# car.net
KiCad netlist of a schematic drawn in Altium Designer
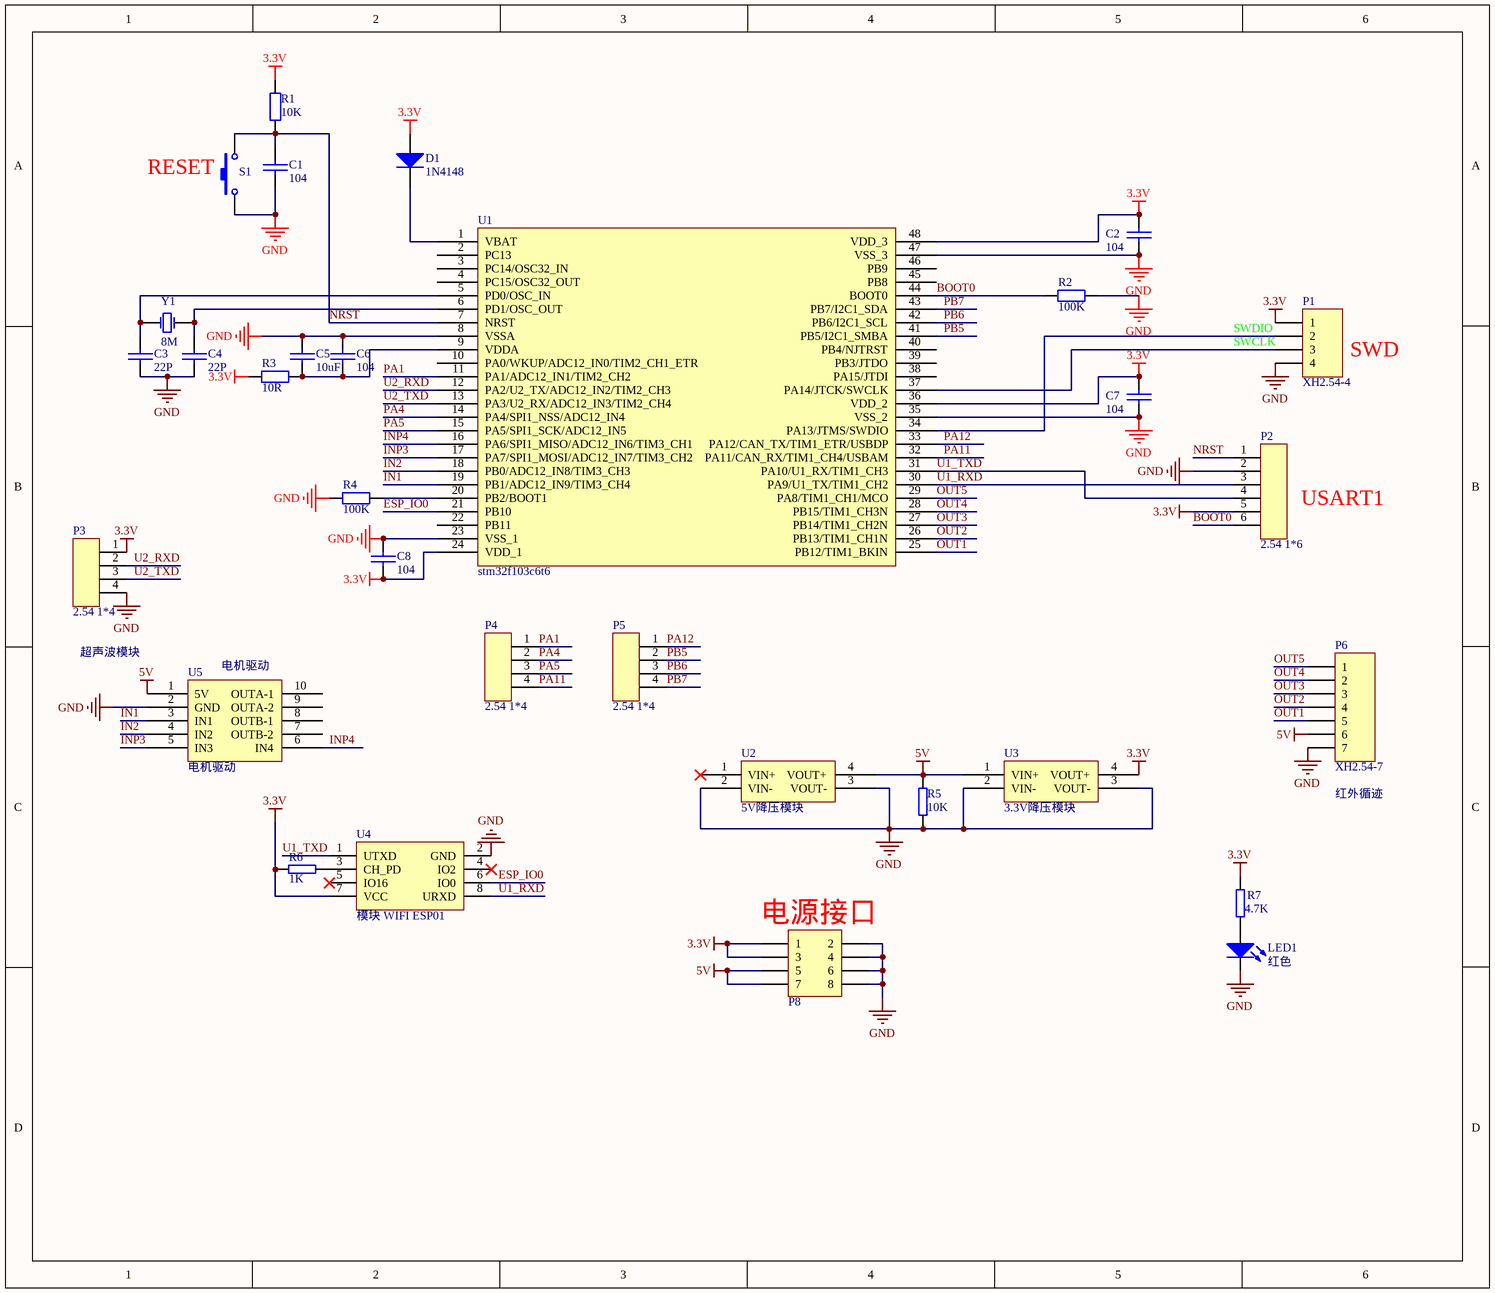
[diagram p0: car.SchDoc]

(export (version "E")
  (design (tool "Eeschema 10.0.6"))
  (components
    (comp (ref "C1") (value "104") (footprint "0805") (libsource (lib "Sch_Device__2010") (part "贴片电容 0805")))
    (comp (ref "C2") (value "104") (footprint "0805") (libsource (lib "Sch_Device__2010") (part "贴片电容 0805")))
    (comp (ref "C3") (value "22P") (footprint "0805") (libsource (lib "Sch_Device__2010") (part "贴片电容 0805")))
    (comp (ref "C4") (value "22P") (footprint "0805") (libsource (lib "Sch_Device__2010") (part "贴片电容 0805")))
    (comp (ref "C5")
      (value "10uF")
      (footprint "1206")
      (libsource (lib "Sch_Device__2010") (part "贴片电容 0805"))
    )
    (comp (ref "C6") (value "104") (footprint "0805") (libsource (lib "Sch_Device__2010") (part "贴片电容 0805")))
    (comp (ref "C7") (value "104") (footprint "0805") (libsource (lib "Sch_Device__2010") (part "贴片电容 0805")))
    (comp (ref "C8") (value "104") (footprint "0805") (libsource (lib "Sch_Device__2010") (part "贴片电容 0805")))
    (comp (ref "D1")
      (value "1N4148")
      (footprint "二极管 贴片 IN4148")
      (libsource (lib "Sch_Device_veryaz") (part "二极管 贴片 1N4148"))
    )
    (comp (ref "LED1")
      (value "红色")
      (footprint "LED0805")
      (libsource (lib "Sch_Device_veryaz") (part "二极管 贴片发光 0805"))
    )
    (comp (ref "P1")
      (value "XH2.54-4")
      (footprint "VH2.54_4")
      (libsource (lib "Sch_Device_veryaz") (part "联结件 XH2.54-4"))
    )
    (comp (ref "P2")
      (value "2.54 1*6")
      (footprint "单排插针 2.54 1*6")
      (libsource (lib "Sch_Device_veryaz") (part "联结件 单排插针 2.54 1*6"))
    )
    (comp (ref "P3")
      (value "2.54 1*4")
      (footprint "单排插针 2.54 1*4")
      (libsource (lib "Sch_Device_veryaz") (part "联结件 单排插针 2.54 1*4"))
    )
    (comp (ref "P4")
      (value "2.54 1*4")
      (footprint "单排插针 2.54 1*4")
      (libsource (lib "Sch_Device_veryaz") (part "联结件 单排插针 2.54 1*4"))
    )
    (comp (ref "P5")
      (value "2.54 1*4")
      (footprint "单排插针 2.54 1*4")
      (libsource (lib "Sch_Device_veryaz") (part "联结件 单排插针 2.54 1*4"))
    )
    (comp (ref "P6")
      (value "XH2.54-7")
      (footprint "VH2.54_7")
      (libsource (lib "Sch_Device_veryaz") (part "联结件 XH2.54-7"))
    )
    (comp (ref "P8")
      (value "双排插针 2.54 2*4")
      (footprint "双排插针 2.54 2*4")
      (libsource (lib "Sch_Device_veryaz") (part "联结件 双排插针 2.54 2*4"))
    )
    (comp (ref "R1")
      (value "10K")
      (footprint "0805")
      (libsource (lib "Sch_Device_veryaz") (part "贴片电阻 0603"))
    )
    (comp (ref "R2") (value "100K") (footprint "0805") (libsource (lib "") (part "贴片电阻 0805_1")))
    (comp (ref "R3") (value "10R") (footprint "0805") (libsource (lib "") (part "贴片电阻 0603_1")))
    (comp (ref "R4")
      (value "100K")
      (footprint "0805")
      (libsource (lib "Sch_Device_Simple") (part "贴片电阻 0805"))
    )
    (comp (ref "R5") (value "10K") (footprint "0805") (libsource (lib "MyLib") (part "电阻 贴片 0805")))
    (comp (ref "R6")
      (value "1K")
      (footprint "0805")
      (libsource (lib "Sch_Device_veryaz") (part "电阻 贴片 0805"))
    )
    (comp (ref "R7") (value "4.7K") (footprint "0805") (libsource (lib "MyLib") (part "电阻 贴片 0805")))
    (comp (ref "S1")
      (value "key")
      (footprint "按键 轻触  6*3")
      (libsource (lib "Sch_Device_veryaz") (part "按键 轻触 3*6"))
    )
    (comp (ref "U1")
      (value "stm32f103c6t6")
      (footprint "STM32F103C6T6")
      (libsource (lib "STM32F103C6T6") (part "stm32f103c6t6"))
    )
    (comp (ref "U2") (value "5V降压模块") (footprint "降压模块") (libsource (lib "MyLib") (part "降压模块")))
    (comp (ref "U3") (value "3.3V降压模块") (footprint "降压模块") (libsource (lib "MyLib") (part "降压模块")))
    (comp (ref "U4")
      (value "模块 WIFI ESP01")
      (footprint "模块 WIFI ESP01")
      (libsource (lib "Sch_Device_veryaz") (part "模块 WIFI ESP01"))
    )
    (comp (ref "U5") (value "电机驱动") (footprint "电机驱动") (libsource (lib "MyLib") (part "电机驱动")))
    (comp (ref "Y1")
      (value "8M")
      (footprint "晶振 BCY-W2/E4.7")
      (libsource (lib "Sch_Device_veryaz") (part "晶振 直插矮"))
    )
  )
  (nets
    (net (code "1") (name "/BOOT0") (class "Default")
      (node (ref "P2") (pin "6") (pinfunction "6_6") (pintype "passive"))
      (node (ref "R2") (pin "2") (pinfunction "2_2") (pintype "passive"))
      (node (ref "U1") (pin "44") (pinfunction "BOOT0_44") (pintype "passive"))
    )
    (net (code "2") (name "/ESP_IO0") (class "Default")
      (node (ref "U1") (pin "21") (pinfunction "PB10_21") (pintype "passive"))
      (node (ref "U4") (pin "6") (pinfunction "IO0_6") (pintype "passive"))
    )
    (net (code "3") (name "/IN1") (class "Default")
      (node (ref "U1") (pin "19") (pinfunction "PB1/ADC12_IN9/TIM3_CH4_19") (pintype "passive"))
      (node (ref "U5") (pin "3") (pinfunction "IN1_3") (pintype "passive"))
    )
    (net (code "4") (name "/IN2") (class "Default")
      (node (ref "U1") (pin "18") (pinfunction "PB0/ADC12_IN8/TIM3_CH3_18") (pintype "passive"))
      (node (ref "U5") (pin "4") (pinfunction "IN2_4") (pintype "passive"))
    )
    (net (code "5") (name "/INP3") (class "Default")
      (node (ref "U1") (pin "17") (pinfunction "PA7/SPI1_MOSI/ADC12_IN7/TIM3_CH2_17") (pintype "passive"))
      (node (ref "U5") (pin "5") (pinfunction "IN3_5") (pintype "passive"))
    )
    (net (code "6") (name "/INP4") (class "Default")
      (node (ref "U1") (pin "16") (pinfunction "PA6/SPI1_MISO/ADC12_IN6/TIM3_CH1_16") (pintype "passive"))
      (node (ref "U5") (pin "6") (pinfunction "IN4_6") (pintype "passive"))
    )
    (net (code "7") (name "/NRST") (class "Default")
      (node (ref "C1") (pin "2") (pintype "passive"))
      (node (ref "P2") (pin "1") (pinfunction "1_1") (pintype "passive"))
      (node (ref "R1") (pin "2") (pinfunction "2_2") (pintype "passive"))
      (node (ref "S1") (pin "2") (pinfunction "2_2") (pintype "passive"))
      (node (ref "U1") (pin "7") (pinfunction "NRST_7") (pintype "passive"))
    )
    (net (code "8") (name "/OUT1") (class "Default")
      (node (ref "P6") (pin "5") (pinfunction "5_5") (pintype "passive"))
      (node (ref "U1") (pin "25") (pinfunction "PB12/TIM1_BKIN_25") (pintype "passive"))
    )
    (net (code "9") (name "/OUT2") (class "Default")
      (node (ref "P6") (pin "4") (pinfunction "4_4") (pintype "passive"))
      (node (ref "U1") (pin "26") (pinfunction "PB13/TIM1_CH1N_26") (pintype "passive"))
    )
    (net (code "10") (name "/OUT3") (class "Default")
      (node (ref "P6") (pin "3") (pinfunction "3_3") (pintype "passive"))
      (node (ref "U1") (pin "27") (pinfunction "PB14/TIM1_CH2N_27") (pintype "passive"))
    )
    (net (code "11") (name "/OUT4") (class "Default")
      (node (ref "P6") (pin "2") (pinfunction "2_2") (pintype "passive"))
      (node (ref "U1") (pin "28") (pinfunction "PB15/TIM1_CH3N_28") (pintype "passive"))
    )
    (net (code "12") (name "/OUT5") (class "Default")
      (node (ref "P6") (pin "1") (pinfunction "1_1") (pintype "passive"))
      (node (ref "U1") (pin "29") (pinfunction "PA8/TIM1_CH1/MCO_29") (pintype "passive"))
    )
    (net (code "13") (name "/PA1") (class "Default")
      (node (ref "P4") (pin "1") (pinfunction "1_1") (pintype "passive"))
      (node (ref "U1") (pin "11") (pinfunction "PA1/ADC12_IN1/TIM2_CH2_11") (pintype "passive"))
    )
    (net (code "14") (name "/PA4") (class "Default")
      (node (ref "P4") (pin "2") (pinfunction "2_2") (pintype "passive"))
      (node (ref "U1") (pin "14") (pinfunction "PA4/SPI1_NSS/ADC12_IN4_14") (pintype "passive"))
    )
    (net (code "15") (name "/PA5") (class "Default")
      (node (ref "P4") (pin "3") (pinfunction "3_3") (pintype "passive"))
      (node (ref "U1") (pin "15") (pinfunction "PA5/SPI1_SCK/ADC12_IN5_15") (pintype "passive"))
    )
    (net (code "16") (name "/PA11") (class "Default")
      (node (ref "P4") (pin "4") (pinfunction "4_4") (pintype "passive"))
      (node (ref "U1") (pin "32") (pinfunction "PA11/CAN_RX/TIM1_CH4/USBAM_32") (pintype "passive"))
    )
    (net (code "17") (name "/PA12") (class "Default")
      (node (ref "P5") (pin "1") (pinfunction "1_1") (pintype "passive"))
      (node (ref "U1") (pin "33") (pinfunction "PA12/CAN_TX/TIM1_ETR/USBDP_33") (pintype "passive"))
    )
    (net (code "18") (name "/PB5") (class "Default")
      (node (ref "P5") (pin "2") (pinfunction "2_2") (pintype "passive"))
      (node (ref "U1") (pin "41") (pinfunction "PB5/I2C1_SMBA_41") (pintype "passive"))
    )
    (net (code "19") (name "/PB6") (class "Default")
      (node (ref "P5") (pin "3") (pinfunction "3_3") (pintype "passive"))
      (node (ref "U1") (pin "42") (pinfunction "PB6/I2C1_SCL_42") (pintype "passive"))
    )
    (net (code "20") (name "/PB7") (class "Default")
      (node (ref "P5") (pin "4") (pinfunction "4_4") (pintype "passive"))
      (node (ref "U1") (pin "43") (pinfunction "PB7/I2C1_SDA_43") (pintype "passive"))
    )
    (net (code "21") (name "/SWCLK") (class "Default")
      (node (ref "P1") (pin "3") (pinfunction "3_3") (pintype "passive"))
      (node (ref "U1") (pin "37") (pinfunction "PA14/JTCK/SWCLK_37") (pintype "passive"))
    )
    (net (code "22") (name "/SWDIO") (class "Default")
      (node (ref "P1") (pin "2") (pinfunction "2_2") (pintype "passive"))
      (node (ref "U1") (pin "34") (pinfunction "PA13/JTMS/SWDIO_34") (pintype "passive"))
    )
    (net (code "23") (name "/U1_RXD") (class "Default")
      (node (ref "P2") (pin "3") (pinfunction "3_3") (pintype "passive"))
      (node (ref "U1") (pin "30") (pinfunction "PA9/U1_TX/TIM1_CH2_30") (pintype "passive"))
      (node (ref "U4") (pin "8") (pinfunction "URXD_8") (pintype "passive"))
    )
    (net (code "24") (name "/U1_TXD") (class "Default")
      (node (ref "P2") (pin "4") (pinfunction "4_4") (pintype "passive"))
      (node (ref "U1") (pin "31") (pinfunction "PA10/U1_RX/TIM1_CH3_31") (pintype "passive"))
      (node (ref "U4") (pin "1") (pinfunction "UTXD_1") (pintype "passive"))
    )
    (net (code "25") (name "/U2_RXD") (class "Default")
      (node (ref "P3") (pin "2") (pinfunction "2_2") (pintype "passive"))
      (node (ref "U1") (pin "12") (pinfunction "PA2/U2_TX/ADC12_IN2/TIM2_CH3_12") (pintype "passive"))
    )
    (net (code "26") (name "/U2_TXD") (class "Default")
      (node (ref "P3") (pin "3") (pinfunction "3_3") (pintype "passive"))
      (node (ref "U1") (pin "13") (pinfunction "PA3/U2_RX/ADC12_IN3/TIM2_CH4_13") (pintype "passive"))
    )
    (net (code "27") (name "3.3V") (class "Default")
      (node (ref "C2") (pin "1") (pintype "passive"))
      (node (ref "C7") (pin "1") (pintype "passive"))
      (node (ref "C8") (pin "1") (pintype "passive"))
      (node (ref "D1") (pin "1") (pinfunction "A_1") (pintype "passive"))
      (node (ref "P1") (pin "1") (pinfunction "1_1") (pintype "passive"))
      (node (ref "P2") (pin "5") (pinfunction "5_5") (pintype "passive"))
      (node (ref "P3") (pin "1") (pinfunction "1_1") (pintype "passive"))
      (node (ref "P8") (pin "1") (pinfunction "1_1") (pintype "passive"))
      (node (ref "P8") (pin "3") (pinfunction "3_3") (pintype "passive"))
      (node (ref "R1") (pin "1") (pinfunction "1_1") (pintype "passive"))
      (node (ref "R3") (pin "1") (pinfunction "1_1") (pintype "passive"))
      (node (ref "R6") (pin "2") (pinfunction "2_2") (pintype "passive"))
      (node (ref "R7") (pin "2") (pinfunction "2_2") (pintype "passive"))
      (node (ref "U1") (pin "24") (pinfunction "VDD_1_24") (pintype "passive"))
      (node (ref "U1") (pin "36") (pinfunction "VDD_2_36") (pintype "passive"))
      (node (ref "U1") (pin "48") (pinfunction "VDD_3_48") (pintype "passive"))
      (node (ref "U3") (pin "4") (pinfunction "VOUT+_4") (pintype "passive"))
      (node (ref "U4") (pin "7") (pinfunction "VCC_7") (pintype "passive"))
    )
    (net (code "28") (name "5V") (class "Default")
      (node (ref "P6") (pin "6") (pinfunction "6_6") (pintype "passive"))
      (node (ref "P8") (pin "5") (pinfunction "5_5") (pintype "passive"))
      (node (ref "P8") (pin "7") (pinfunction "7_7") (pintype "passive"))
      (node (ref "R5") (pin "2") (pinfunction "2_2") (pintype "passive"))
      (node (ref "U2") (pin "4") (pinfunction "VOUT+_4") (pintype "passive"))
      (node (ref "U3") (pin "1") (pinfunction "VIN+_1") (pintype "passive"))
      (node (ref "U5") (pin "1") (pinfunction "5V_1") (pintype "passive"))
    )
    (net (code "29") (name "GND") (class "Default")
      (node (ref "C1") (pin "1") (pintype "passive"))
      (node (ref "C2") (pin "2") (pintype "passive"))
      (node (ref "C3") (pin "1") (pintype "passive"))
      (node (ref "C4") (pin "1") (pintype "passive"))
      (node (ref "C5") (pin "2") (pintype "passive"))
      (node (ref "C6") (pin "2") (pintype "passive"))
      (node (ref "C7") (pin "2") (pintype "passive"))
      (node (ref "C8") (pin "2") (pintype "passive"))
      (node (ref "LED1") (pin "2") (pinfunction "K_2") (pintype "passive"))
      (node (ref "P1") (pin "4") (pinfunction "4_4") (pintype "passive"))
      (node (ref "P2") (pin "2") (pinfunction "2_2") (pintype "passive"))
      (node (ref "P3") (pin "4") (pinfunction "4_4") (pintype "passive"))
      (node (ref "P6") (pin "7") (pinfunction "7_7") (pintype "passive"))
      (node (ref "P8") (pin "2") (pinfunction "2_2") (pintype "passive"))
      (node (ref "P8") (pin "4") (pinfunction "4_4") (pintype "passive"))
      (node (ref "P8") (pin "6") (pinfunction "6_6") (pintype "passive"))
      (node (ref "P8") (pin "8") (pinfunction "8_8") (pintype "passive"))
      (node (ref "R2") (pin "1") (pinfunction "1_1") (pintype "passive"))
      (node (ref "R4") (pin "1") (pinfunction "1_1") (pintype "passive"))
      (node (ref "R5") (pin "1") (pinfunction "1_1") (pintype "passive"))
      (node (ref "S1") (pin "1") (pinfunction "1_1") (pintype "passive"))
      (node (ref "U1") (pin "23") (pinfunction "VSS_1_23") (pintype "passive"))
      (node (ref "U1") (pin "35") (pinfunction "VSS_2_35") (pintype "passive"))
      (node (ref "U1") (pin "47") (pinfunction "VSS_3_47") (pintype "passive"))
      (node (ref "U1") (pin "8") (pinfunction "VSSA_8") (pintype "passive"))
      (node (ref "U2") (pin "2") (pinfunction "VIN-_2") (pintype "passive"))
      (node (ref "U2") (pin "3") (pinfunction "VOUT-_3") (pintype "passive"))
      (node (ref "U3") (pin "2") (pinfunction "VIN-_2") (pintype "passive"))
      (node (ref "U3") (pin "3") (pinfunction "VOUT-_3") (pintype "passive"))
      (node (ref "U4") (pin "2") (pinfunction "GND_2") (pintype "passive"))
      (node (ref "U5") (pin "2") (pinfunction "GND_2") (pintype "passive"))
    )
    (net (code "30") (name "Net-(D1-K)") (class "Default")
      (node (ref "D1") (pin "2") (pinfunction "K_2") (pintype "passive"))
      (node (ref "U1") (pin "1") (pinfunction "VBAT_1") (pintype "passive"))
    )
    (net (code "31") (name "Net-(LED1-A)") (class "Default")
      (node (ref "LED1") (pin "1") (pinfunction "A_1") (pintype "passive"))
      (node (ref "R7") (pin "1") (pinfunction "1_1") (pintype "passive"))
    )
    (net (code "32") (name "Net-(U1-PB2{slash}BOOT1)") (class "Default")
      (node (ref "R4") (pin "2") (pinfunction "2_2") (pintype "passive"))
      (node (ref "U1") (pin "20") (pinfunction "PB2/BOOT1_20") (pintype "passive"))
    )
    (net (code "33") (name "Net-(U1-PD0{slash}OSC_IN)") (class "Default")
      (node (ref "C3") (pin "2") (pintype "passive"))
      (node (ref "U1") (pin "5") (pinfunction "PD0/OSC_IN_5") (pintype "passive"))
      (node (ref "Y1") (pin "2") (pinfunction "OSC2_2") (pintype "passive"))
    )
    (net (code "34") (name "Net-(U1-PD1{slash}OSC_OUT)") (class "Default")
      (node (ref "C4") (pin "2") (pintype "passive"))
      (node (ref "U1") (pin "6") (pinfunction "PD1/OSC_OUT_6") (pintype "passive"))
      (node (ref "Y1") (pin "1") (pinfunction "OSC1_1") (pintype "passive"))
    )
    (net (code "35") (name "Net-(U1-VDDA)") (class "Default")
      (node (ref "C5") (pin "1") (pintype "passive"))
      (node (ref "C6") (pin "1") (pintype "passive"))
      (node (ref "R3") (pin "2") (pinfunction "2_2") (pintype "passive"))
      (node (ref "U1") (pin "9") (pinfunction "VDDA_9") (pintype "passive"))
    )
    (net (code "36") (name "Net-(U4-CH_PD)") (class "Default")
      (node (ref "R6") (pin "1") (pinfunction "1_1") (pintype "passive"))
      (node (ref "U4") (pin "3") (pinfunction "CH_PD_3") (pintype "passive"))
    )
    (net (code "37") (name "unconnected-(U1-PA0{slash}WKUP{slash}ADC12_IN0{slash}TIM2_CH1_ETR-Pad10)") (class "Default")
      (node (ref "U1") (pin "10") (pinfunction "PA0/WKUP/ADC12_IN0/TIM2_CH1_ETR_10") (pintype "passive"))
    )
    (net (code "38") (name "unconnected-(U1-PA15{slash}JTDI-Pad38)") (class "Default")
      (node (ref "U1") (pin "38") (pinfunction "PA15/JTDI_38") (pintype "passive"))
    )
    (net (code "39") (name "unconnected-(U1-PB3{slash}JTDO-Pad39)") (class "Default")
      (node (ref "U1") (pin "39") (pinfunction "PB3/JTDO_39") (pintype "passive"))
    )
    (net (code "40") (name "unconnected-(U1-PB4{slash}NJTRST-Pad40)") (class "Default")
      (node (ref "U1") (pin "40") (pinfunction "PB4/NJTRST_40") (pintype "passive"))
    )
    (net (code "41") (name "unconnected-(U1-PB8-Pad45)") (class "Default")
      (node (ref "U1") (pin "45") (pinfunction "PB8_45") (pintype "passive"))
    )
    (net (code "42") (name "unconnected-(U1-PB9-Pad46)") (class "Default")
      (node (ref "U1") (pin "46") (pinfunction "PB9_46") (pintype "passive"))
    )
    (net (code "43") (name "unconnected-(U1-PB11-Pad22)") (class "Default")
      (node (ref "U1") (pin "22") (pinfunction "PB11_22") (pintype "passive"))
    )
    (net (code "44") (name "unconnected-(U1-PC13-Pad2)") (class "Default")
      (node (ref "U1") (pin "2") (pinfunction "PC13_2") (pintype "passive"))
    )
    (net (code "45") (name "unconnected-(U1-PC14{slash}OSC32_IN-Pad3)") (class "Default")
      (node (ref "U1") (pin "3") (pinfunction "PC14/OSC32_IN_3") (pintype "passive"))
    )
    (net (code "46") (name "unconnected-(U1-PC15{slash}OSC32_OUT-Pad4)") (class "Default")
      (node (ref "U1") (pin "4") (pinfunction "PC15/OSC32_OUT_4") (pintype "passive"))
    )
    (net (code "47") (name "unconnected-(U2-VIN+-Pad1)") (class "Default")
      (node (ref "U2") (pin "1") (pinfunction "VIN+_1") (pintype "passive+no_connect"))
    )
    (net (code "48") (name "unconnected-(U4-IO2-Pad4)") (class "Default")
      (node (ref "U4") (pin "4") (pinfunction "IO2_4") (pintype "passive+no_connect"))
    )
    (net (code "49") (name "unconnected-(U4-IO16-Pad5)") (class "Default")
      (node (ref "U4") (pin "5") (pinfunction "IO16_5") (pintype "passive+no_connect"))
    )
    (net (code "50") (name "unconnected-(U5-OUTA-1-Pad10)") (class "Default")
      (node (ref "U5") (pin "10") (pinfunction "OUTA-1_10") (pintype "passive"))
    )
    (net (code "51") (name "unconnected-(U5-OUTA-2-Pad9)") (class "Default")
      (node (ref "U5") (pin "9") (pinfunction "OUTA-2_9") (pintype "passive"))
    )
    (net (code "52") (name "unconnected-(U5-OUTB-1-Pad8)") (class "Default")
      (node (ref "U5") (pin "8") (pinfunction "OUTB-1_8") (pintype "passive"))
    )
    (net (code "53") (name "unconnected-(U5-OUTB-2-Pad7)") (class "Default")
      (node (ref "U5") (pin "7") (pinfunction "OUTB-2_7") (pintype "passive"))
    )
  )
)
